# Smartfin_Main_PCBA_GPS.net
KiCad netlist of a schematic drawn in Altium Designer
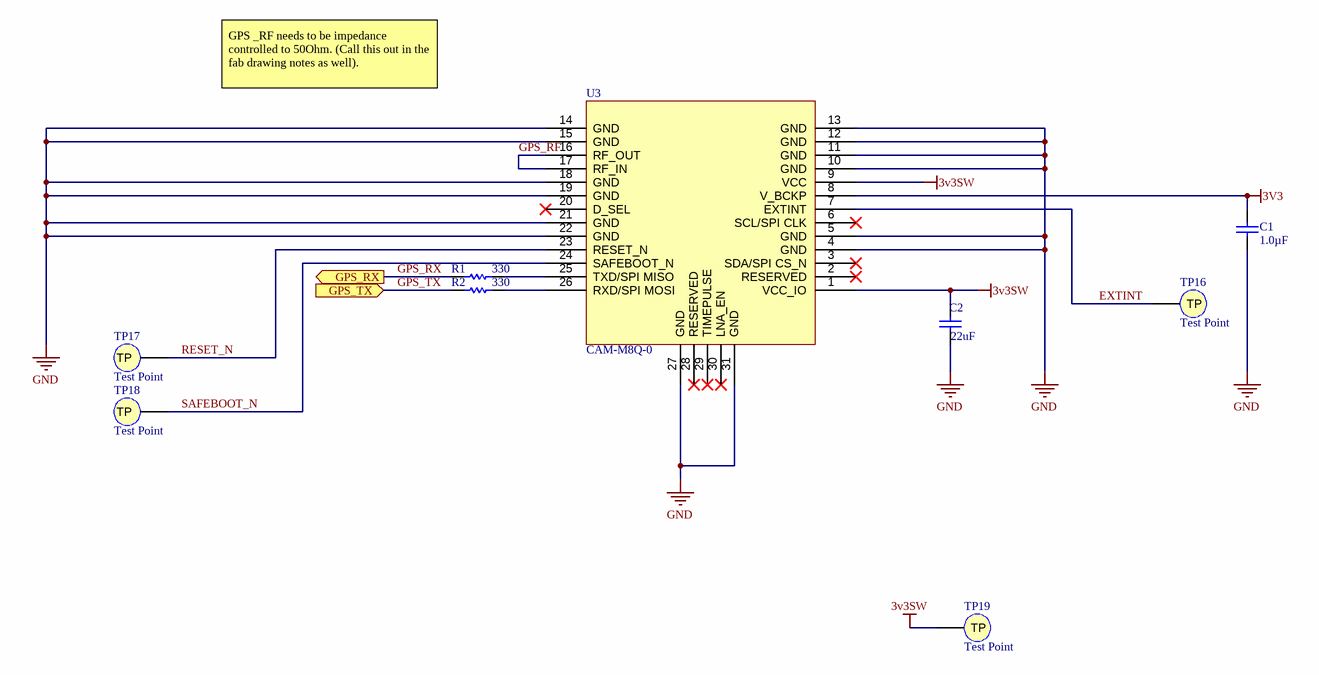
[diagram p0: Smartfin Main PCBA GPS.SchDoc]

(export (version "E")
  (design (tool "Eeschema 10.0.6"))
  (components
    (comp (ref "C1")
      (value "1.0µF")
      (footprint "CAPC0402(1005)60_N")
      (description "CAP CER 1UF 10V 10% X5R 0402")
      (fields
        (field (name "MANUFACTURER") "Yageo")
        (field (name "MANUFACTURER PART NUMBER") "CC0402KRX5R6BB105")
      )
      (libsource (lib "Syncroness Vault") (part "CAP"))
    )
    (comp (ref "C2")
      (value "22uF")
      (footprint "CAPC0603(1608)100_N")
      (description "CAP CER 22UF 10V X5R 0603")
      (fields (field (name "TOLERANCE") "20%") (field (name "MANUFACTURER") "Murata Electronics"))
      (libsource (lib "Syncroness Vault") (part "CAP"))
    )
    (comp (ref "R1")
      (value "330")
      (footprint "RESC1005X04N")
      (description "RES SMD 330 OHM 1% 1/16W 0402")
      (fields
        (field (name "MANUFACTURER") "Vishay Dale")
        (field (name "MANUFACTURER PART NUMBER") "CRCW0402330RFKED")
      )
      (libsource (lib "Syncroness Vault") (part "RES"))
    )
    (comp (ref "R2")
      (value "330")
      (footprint "RESC1005X04N")
      (description "RES SMD 330 OHM 1% 1/16W 0402")
      (fields
        (field (name "MANUFACTURER") "Vishay Dale")
        (field (name "MANUFACTURER PART NUMBER") "CRCW0402330RFKED")
      )
      (libsource (lib "Syncroness Vault") (part "RES"))
    )
    (comp (ref "TP16")
      (value "Test Point")
      (footprint "TESTPAD_ICT")
      (description "ICT Test Point")
      (libsource (lib "Syncroness Vault") (part "TestPointPadOnly"))
    )
    (comp (ref "TP17")
      (value "Test Point")
      (footprint "TESTPAD_ICT")
      (description "ICT Test Point")
      (libsource (lib "Syncroness Vault") (part "TestPointPadOnly"))
    )
    (comp (ref "TP18")
      (value "Test Point")
      (footprint "TESTPAD_ICT")
      (description "ICT Test Point")
      (libsource (lib "Syncroness Vault") (part "TestPointPadOnly"))
    )
    (comp (ref "TP19")
      (value "Test Point")
      (footprint "TESTPAD_ICT")
      (description "ICT Test Point")
      (libsource (lib "Syncroness Vault") (part "TestPointPadOnly"))
    )
    (comp (ref "U3")
      (value "CAM-M8Q-0")
      (footprint "CAM-M8Q-0-Footprint-1")
      (description "RF RCVR GNSS/GPS 1.575GHZ MODULE")
      (fields (field (name "MANUFACTURER") "U-Blox"))
      (libsource (lib "Syncroness Vault") (part "CAM-M8Q-0"))
    )
  )
  (nets
    (net (code "1") (name "/EXTINT") (class "Default")
      (node (ref "TP16") (pin "1") (pinfunction "TP_1") (pintype "passive"))
      (node (ref "U3") (pin "7") (pinfunction "EXTINT_7") (pintype "passive"))
    )
    (net (code "2") (name "/GPS_RF") (class "Default")
      (node (ref "U3") (pin "16") (pinfunction "RF_OUT_16") (pintype "passive"))
      (node (ref "U3") (pin "17") (pinfunction "RF_IN_17") (pintype "passive"))
    )
    (net (code "3") (name "/GPS_RX") (class "Default")
      (node (ref "R1") (pin "1") (pinfunction "1_1") (pintype "passive"))
    )
    (net (code "4") (name "/GPS_TX") (class "Default")
      (node (ref "R2") (pin "1") (pinfunction "1_1") (pintype "passive"))
    )
    (net (code "5") (name "/RESET_N") (class "Default")
      (node (ref "TP17") (pin "1") (pinfunction "TP_1") (pintype "passive"))
      (node (ref "U3") (pin "23") (pinfunction "RESET_N_23") (pintype "passive"))
    )
    (net (code "6") (name "/SAFEBOOT_N") (class "Default")
      (node (ref "TP18") (pin "1") (pinfunction "TP_1") (pintype "passive"))
      (node (ref "U3") (pin "24") (pinfunction "SAFEBOOT_N_24") (pintype "passive"))
    )
    (net (code "7") (name "3V3") (class "Default")
      (node (ref "C1") (pin "2") (pinfunction "2_2") (pintype "passive"))
      (node (ref "U3") (pin "8") (pinfunction "V_BCKP_8") (pintype "passive"))
    )
    (net (code "8") (name "3v3SW") (class "Default")
      (node (ref "C2") (pin "2") (pinfunction "2_2") (pintype "passive"))
      (node (ref "TP19") (pin "1") (pinfunction "TP_1") (pintype "passive"))
      (node (ref "U3") (pin "1") (pinfunction "VCC_IO_1") (pintype "power_in"))
      (node (ref "U3") (pin "9") (pinfunction "VCC_9") (pintype "power_in"))
    )
    (net (code "9") (name "GND") (class "Default")
      (node (ref "C1") (pin "1") (pinfunction "1_1") (pintype "passive"))
      (node (ref "C2") (pin "1") (pinfunction "1_1") (pintype "passive"))
      (node (ref "U3") (pin "10") (pinfunction "GND_10") (pintype "power_in"))
      (node (ref "U3") (pin "11") (pinfunction "GND_11") (pintype "power_in"))
      (node (ref "U3") (pin "12") (pinfunction "GND_12") (pintype "power_in"))
      (node (ref "U3") (pin "13") (pinfunction "GND_13") (pintype "power_in"))
      (node (ref "U3") (pin "14") (pinfunction "GND_14") (pintype "power_in"))
      (node (ref "U3") (pin "15") (pinfunction "GND_15") (pintype "power_in"))
      (node (ref "U3") (pin "18") (pinfunction "GND_18") (pintype "power_in"))
      (node (ref "U3") (pin "19") (pinfunction "GND_19") (pintype "power_in"))
      (node (ref "U3") (pin "21") (pinfunction "GND_21") (pintype "power_in"))
      (node (ref "U3") (pin "22") (pinfunction "GND_22") (pintype "power_in"))
      (node (ref "U3") (pin "27") (pinfunction "GND_27") (pintype "power_in"))
      (node (ref "U3") (pin "31") (pinfunction "GND_31") (pintype "power_in"))
      (node (ref "U3") (pin "4") (pinfunction "GND_4") (pintype "power_in"))
      (node (ref "U3") (pin "5") (pinfunction "GND_5") (pintype "power_in"))
    )
    (net (code "10") (name "Net-(U3-RXD{slash}SPI_MOSI)") (class "Default")
      (node (ref "R2") (pin "2") (pinfunction "2_2") (pintype "passive"))
      (node (ref "U3") (pin "26") (pinfunction "RXD/SPI_MOSI_26") (pintype "passive"))
    )
    (net (code "11") (name "Net-(U3-TXD{slash}SPI_MISO)") (class "Default")
      (node (ref "R1") (pin "2") (pinfunction "2_2") (pintype "passive"))
      (node (ref "U3") (pin "25") (pinfunction "TXD/SPI_MISO_25") (pintype "passive"))
    )
    (net (code "12") (name "unconnected-(U3-D_SEL-Pad20)") (class "Default")
      (node (ref "U3") (pin "20") (pinfunction "D_SEL_20") (pintype "passive+no_connect"))
    )
    (net (code "13") (name "unconnected-(U3-LNA_EN-Pad30)") (class "Default")
      (node (ref "U3") (pin "30") (pinfunction "LNA_EN_30") (pintype "passive+no_connect"))
    )
    (net (code "14") (name "unconnected-(U3-RESERVED-Pad2)") (class "Default")
      (node (ref "U3") (pin "2") (pinfunction "RESERVED_2") (pintype "passive+no_connect"))
    )
    (net (code "15") (name "unconnected-(U3-RESERVED-Pad28)") (class "Default")
      (node (ref "U3") (pin "28") (pinfunction "RESERVED_28") (pintype "passive+no_connect"))
    )
    (net (code "16") (name "unconnected-(U3-SCL{slash}SPI_CLK-Pad6)") (class "Default")
      (node (ref "U3") (pin "6") (pinfunction "SCL/SPI_CLK_6") (pintype "passive+no_connect"))
    )
    (net (code "17") (name "unconnected-(U3-SDA{slash}SPI_CS_N-Pad3)") (class "Default")
      (node (ref "U3") (pin "3") (pinfunction "SDA/SPI_CS_N_3") (pintype "passive+no_connect"))
    )
    (net (code "18") (name "unconnected-(U3-TIMEPULSE-Pad29)") (class "Default")
      (node (ref "U3") (pin "29") (pinfunction "TIMEPULSE_29") (pintype "passive+no_connect"))
    )
  )
)
